# LedTile.net
KiCad netlist of a schematic drawn in EAGLE
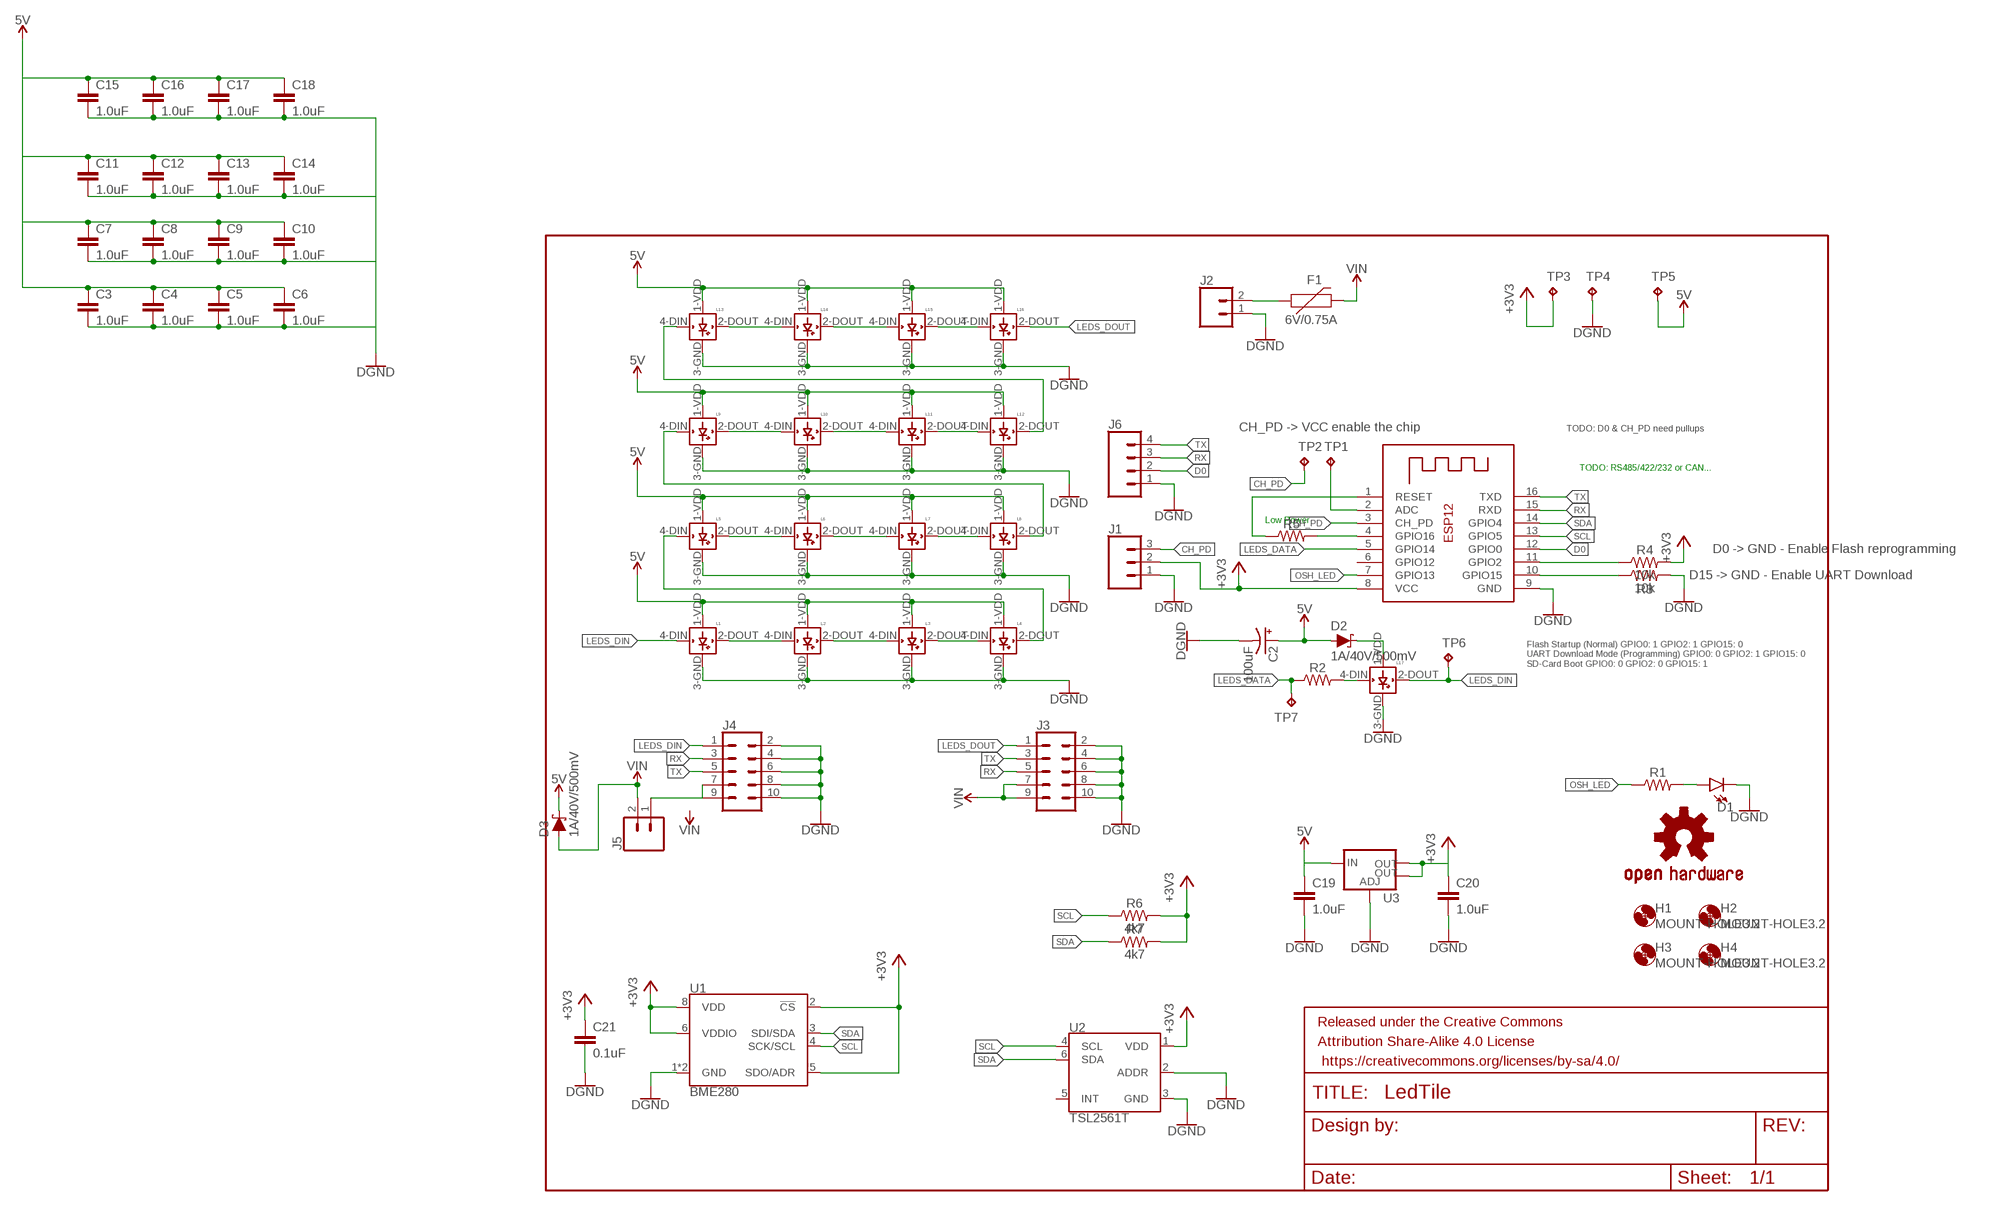
[diagram p0: schematic, sheet 1]

(export (version "E")
  (design (tool "Eeschema 10.0.6"))
  (components
    (comp (ref "C2")
      (value "100uF")
      (footprint "eagle-import:EIA7343")
      (libsource (lib "eagle-import") (part "100UF-POLAR-EIA7343-10V-10%(TANT)"))
    )
    (comp (ref "C3")
      (value "1.0uF")
      (footprint "eagle-import:0805")
      (libsource (lib "eagle-import") (part "1.0UF-0805-25V-(+80/-20%)"))
    )
    (comp (ref "C4")
      (value "1.0uF")
      (footprint "eagle-import:0805")
      (libsource (lib "eagle-import") (part "1.0UF-0805-25V-(+80/-20%)"))
    )
    (comp (ref "C5")
      (value "1.0uF")
      (footprint "eagle-import:0805")
      (libsource (lib "eagle-import") (part "1.0UF-0805-25V-(+80/-20%)"))
    )
    (comp (ref "C6")
      (value "1.0uF")
      (footprint "eagle-import:0805")
      (libsource (lib "eagle-import") (part "1.0UF-0805-25V-(+80/-20%)"))
    )
    (comp (ref "C7")
      (value "1.0uF")
      (footprint "eagle-import:0805")
      (libsource (lib "eagle-import") (part "1.0UF-0805-25V-(+80/-20%)"))
    )
    (comp (ref "C8")
      (value "1.0uF")
      (footprint "eagle-import:0805")
      (libsource (lib "eagle-import") (part "1.0UF-0805-25V-(+80/-20%)"))
    )
    (comp (ref "C9")
      (value "1.0uF")
      (footprint "eagle-import:0805")
      (libsource (lib "eagle-import") (part "1.0UF-0805-25V-(+80/-20%)"))
    )
    (comp (ref "C10")
      (value "1.0uF")
      (footprint "eagle-import:0805")
      (libsource (lib "eagle-import") (part "1.0UF-0805-25V-(+80/-20%)"))
    )
    (comp (ref "C11")
      (value "1.0uF")
      (footprint "eagle-import:0805")
      (libsource (lib "eagle-import") (part "1.0UF-0805-25V-(+80/-20%)"))
    )
    (comp (ref "C12")
      (value "1.0uF")
      (footprint "eagle-import:0805")
      (libsource (lib "eagle-import") (part "1.0UF-0805-25V-(+80/-20%)"))
    )
    (comp (ref "C13")
      (value "1.0uF")
      (footprint "eagle-import:0805")
      (libsource (lib "eagle-import") (part "1.0UF-0805-25V-(+80/-20%)"))
    )
    (comp (ref "C14")
      (value "1.0uF")
      (footprint "eagle-import:0805")
      (libsource (lib "eagle-import") (part "1.0UF-0805-25V-(+80/-20%)"))
    )
    (comp (ref "C15")
      (value "1.0uF")
      (footprint "eagle-import:0805")
      (libsource (lib "eagle-import") (part "1.0UF-0805-25V-(+80/-20%)"))
    )
    (comp (ref "C16")
      (value "1.0uF")
      (footprint "eagle-import:0805")
      (libsource (lib "eagle-import") (part "1.0UF-0805-25V-(+80/-20%)"))
    )
    (comp (ref "C17")
      (value "1.0uF")
      (footprint "eagle-import:0805")
      (libsource (lib "eagle-import") (part "1.0UF-0805-25V-(+80/-20%)"))
    )
    (comp (ref "C18")
      (value "1.0uF")
      (footprint "eagle-import:0805")
      (libsource (lib "eagle-import") (part "1.0UF-0805-25V-(+80/-20%)"))
    )
    (comp (ref "C19")
      (value "1.0uF")
      (footprint "eagle-import:0805")
      (libsource (lib "eagle-import") (part "1.0UF-0805-25V-(+80/-20%)"))
    )
    (comp (ref "C20")
      (value "1.0uF")
      (footprint "eagle-import:0805")
      (libsource (lib "eagle-import") (part "1.0UF-0805-25V-(+80/-20%)"))
    )
    (comp (ref "C21")
      (value "0.1uF")
      (footprint "eagle-import:0805")
      (libsource (lib "eagle-import") (part "1.0UF-0805-25V-(+80/-20%)"))
    )
    (comp (ref "D1")
      (value "LED1206-BOTTOM")
      (footprint "eagle-import:LED-1206-BOTTOM")
      (libsource (lib "eagle-import") (part "LED1206-BOTTOM"))
    )
    (comp (ref "D2")
      (value "1A/40V/500mV")
      (footprint "eagle-import:SMA-DIODE")
      (libsource (lib "eagle-import") (part "DIODE-SCHOTTKY-SS14"))
    )
    (comp (ref "D3")
      (value "1A/40V/500mV")
      (footprint "eagle-import:SMA-DIODE")
      (libsource (lib "eagle-import") (part "DIODE-SCHOTTKY-SS14"))
    )
    (comp (ref "F1")
      (value "6V/0.75A")
      (footprint "eagle-import:1206")
      (libsource (lib "eagle-import") (part "PPTC_THREE-QUARTER-AMP"))
    )
    (comp (ref "FRAME1")
      (value "FRAME-LETTER")
      (footprint "eagle-import:CREATIVE_COMMONS")
      (libsource (lib "eagle-import") (part "FRAME-LETTER"))
    )
    (comp (ref "H1")
      (value "MOUNT-HOLE3.2")
      (footprint "eagle-import:3,2")
      (libsource (lib "eagle-import") (part "MOUNT-HOLE3.2"))
    )
    (comp (ref "H2")
      (value "MOUNT-HOLE3.2")
      (footprint "eagle-import:3,2")
      (libsource (lib "eagle-import") (part "MOUNT-HOLE3.2"))
    )
    (comp (ref "H3")
      (value "MOUNT-HOLE3.2")
      (footprint "eagle-import:3,2")
      (libsource (lib "eagle-import") (part "MOUNT-HOLE3.2"))
    )
    (comp (ref "H4")
      (value "MOUNT-HOLE3.2")
      (footprint "eagle-import:3,2")
      (libsource (lib "eagle-import") (part "MOUNT-HOLE3.2"))
    )
    (comp (ref "J1")
      (value "CONN_031X03_NO_SILK")
      (footprint "eagle-import:1X03_NO_SILK")
      (libsource (lib "eagle-import") (part "CONN_031X03_NO_SILK"))
    )
    (comp (ref "J2")
      (value "CONN_025MM")
      (footprint "eagle-import:SCREWTERMINAL-5MM-2")
      (libsource (lib "eagle-import") (part "CONN_025MM"))
    )
    (comp (ref "J3")
      (value "CONN_05X2RA")
      (footprint "eagle-import:2X5-RA")
      (libsource (lib "eagle-import") (part "CONN_05X2RA"))
    )
    (comp (ref "J4")
      (value "CONN_05X2RA")
      (footprint "eagle-import:2X5-RA")
      (libsource (lib "eagle-import") (part "CONN_05X2RA"))
    )
    (comp (ref "J5")
      (value "CONN_02")
      (footprint "eagle-import:1X02")
      (libsource (lib "eagle-import") (part "CONN_02"))
    )
    (comp (ref "J6")
      (value "CONN_04")
      (footprint "eagle-import:1X04")
      (libsource (lib "eagle-import") (part "CONN_04"))
    )
    (comp (ref "L1")
      (value "WS2812B")
      (footprint "eagle-import:WS2812B")
      (libsource (lib "eagle-import") (part "WS2812B"))
    )
    (comp (ref "L2")
      (value "WS2812B")
      (footprint "eagle-import:WS2812B")
      (libsource (lib "eagle-import") (part "WS2812B"))
    )
    (comp (ref "L3")
      (value "WS2812B")
      (footprint "eagle-import:WS2812B")
      (libsource (lib "eagle-import") (part "WS2812B"))
    )
    (comp (ref "L4")
      (value "WS2812B")
      (footprint "eagle-import:WS2812B")
      (libsource (lib "eagle-import") (part "WS2812B"))
    )
    (comp (ref "L5")
      (value "WS2812B")
      (footprint "eagle-import:WS2812B")
      (libsource (lib "eagle-import") (part "WS2812B"))
    )
    (comp (ref "L6")
      (value "WS2812B")
      (footprint "eagle-import:WS2812B")
      (libsource (lib "eagle-import") (part "WS2812B"))
    )
    (comp (ref "L7")
      (value "WS2812B")
      (footprint "eagle-import:WS2812B")
      (libsource (lib "eagle-import") (part "WS2812B"))
    )
    (comp (ref "L8")
      (value "WS2812B")
      (footprint "eagle-import:WS2812B")
      (libsource (lib "eagle-import") (part "WS2812B"))
    )
    (comp (ref "L9")
      (value "WS2812B")
      (footprint "eagle-import:WS2812B")
      (libsource (lib "eagle-import") (part "WS2812B"))
    )
    (comp (ref "L10")
      (value "WS2812B")
      (footprint "eagle-import:WS2812B")
      (libsource (lib "eagle-import") (part "WS2812B"))
    )
    (comp (ref "L11")
      (value "WS2812B")
      (footprint "eagle-import:WS2812B")
      (libsource (lib "eagle-import") (part "WS2812B"))
    )
    (comp (ref "L12")
      (value "WS2812B")
      (footprint "eagle-import:WS2812B")
      (libsource (lib "eagle-import") (part "WS2812B"))
    )
    (comp (ref "L13")
      (value "WS2812B")
      (footprint "eagle-import:WS2812B")
      (libsource (lib "eagle-import") (part "WS2812B"))
    )
    (comp (ref "L14")
      (value "WS2812B")
      (footprint "eagle-import:WS2812B")
      (libsource (lib "eagle-import") (part "WS2812B"))
    )
    (comp (ref "L15")
      (value "WS2812B")
      (footprint "eagle-import:WS2812B")
      (libsource (lib "eagle-import") (part "WS2812B"))
    )
    (comp (ref "L16")
      (value "WS2812B")
      (footprint "eagle-import:WS2812B")
      (libsource (lib "eagle-import") (part "WS2812B"))
    )
    (comp (ref "L17")
      (value "WS2812B")
      (footprint "eagle-import:WS2812B")
      (libsource (lib "eagle-import") (part "WS2812B"))
    )
    (comp (ref "LOGO1")
      (value "OSHW-LOGOL")
      (footprint "eagle-import:OSHW-LOGO-L")
      (libsource (lib "eagle-import") (part "OSHW-LOGOL"))
    )
    (comp (ref "R1")
      (value "RESISTOR0805")
      (footprint "eagle-import:0805")
      (libsource (lib "eagle-import") (part "RESISTOR0805"))
    )
    (comp (ref "R2")
      (value "RESISTOR0805")
      (footprint "eagle-import:0805")
      (libsource (lib "eagle-import") (part "RESISTOR0805"))
    )
    (comp (ref "R3")
      (value "10k")
      (footprint "eagle-import:0805")
      (libsource (lib "eagle-import") (part "RESISTOR0805"))
    )
    (comp (ref "R4")
      (value "10k")
      (footprint "eagle-import:0805")
      (libsource (lib "eagle-import") (part "RESISTOR0805"))
    )
    (comp (ref "R5")
      (value "RESISTOR0805")
      (footprint "eagle-import:0805")
      (libsource (lib "eagle-import") (part "RESISTOR0805"))
    )
    (comp (ref "R6")
      (value "4k7")
      (footprint "eagle-import:0805")
      (libsource (lib "eagle-import") (part "RESISTOR0805"))
    )
    (comp (ref "R7")
      (value "4k7")
      (footprint "eagle-import:0805")
      (libsource (lib "eagle-import") (part "RESISTOR0805"))
    )
    (comp (ref "TP1")
      (value "TPTP12R")
      (footprint "eagle-import:TP12R")
      (libsource (lib "eagle-import") (part "TPTP12R"))
    )
    (comp (ref "TP2")
      (value "TPTP12R")
      (footprint "eagle-import:TP12R")
      (libsource (lib "eagle-import") (part "TPTP12R"))
    )
    (comp (ref "TP3")
      (value "TPTP12R")
      (footprint "eagle-import:TP12R")
      (libsource (lib "eagle-import") (part "TPTP12R"))
    )
    (comp (ref "TP4")
      (value "TPTP12R")
      (footprint "eagle-import:TP12R")
      (libsource (lib "eagle-import") (part "TPTP12R"))
    )
    (comp (ref "TP5")
      (value "TPTP12R")
      (footprint "eagle-import:TP12R")
      (libsource (lib "eagle-import") (part "TPTP12R"))
    )
    (comp (ref "TP6")
      (value "TPTP12R")
      (footprint "eagle-import:TP12R")
      (libsource (lib "eagle-import") (part "TPTP12R"))
    )
    (comp (ref "TP7")
      (value "TPTP12R")
      (footprint "eagle-import:TP12R")
      (libsource (lib "eagle-import") (part "TPTP12R"))
    )
    (comp (ref "U1")
      (value "BME280")
      (footprint "eagle-import:LGA-8-2.5X2.5")
      (libsource (lib "eagle-import") (part "BME280"))
    )
    (comp (ref "U2")
      (value "TSL2561T")
      (footprint "eagle-import:TMB-6")
      (libsource (lib "eagle-import") (part "TSL2561T"))
    )
    (comp (ref "U3")
      (value "V_REG_LM1117SOT223")
      (footprint "eagle-import:SOT223")
      (libsource (lib "eagle-import") (part "V_REG_LM1117SOT223"))
    )
    (comp (ref "X1")
      (value "ESP-12")
      (footprint "eagle-import:ESP-12")
      (libsource (lib "eagle-import") (part "ESP-12"))
    )
  )
  (nets
    (net (code "1") (name "+3V3") (class "Default")
      (node (ref "C20") (pin "1") (pinfunction "1_1") (pintype "passive"))
      (node (ref "C21") (pin "1") (pinfunction "1_1") (pintype "passive"))
      (node (ref "J1") (pin "2") (pinfunction "2_2") (pintype "passive"))
      (node (ref "R4") (pin "2") (pinfunction "2_2") (pintype "passive"))
      (node (ref "R6") (pin "2") (pinfunction "2_2") (pintype "passive"))
      (node (ref "R7") (pin "2") (pinfunction "2_2") (pintype "passive"))
      (node (ref "TP3") (pin "TP") (pinfunction "TP_TP") (pintype "input"))
      (node (ref "U1") (pin "2") (pinfunction "~{CS}_2") (pintype "bidirectional"))
      (node (ref "U1") (pin "5") (pinfunction "SDO/ADR_5") (pintype "bidirectional"))
      (node (ref "U1") (pin "6") (pinfunction "VDDIO_6") (pintype "bidirectional"))
      (node (ref "U1") (pin "8") (pinfunction "VDD_8") (pintype "bidirectional"))
      (node (ref "U2") (pin "1") (pinfunction "VDD_1") (pintype "power_in"))
      (node (ref "U3") (pin "2") (pinfunction "OUT_2") (pintype "output"))
      (node (ref "U3") (pin "4") (pinfunction "OUT_4") (pintype "output"))
      (node (ref "X1") (pin "8") (pinfunction "VCC_8") (pintype "power_in"))
    )
    (net (code "2") (name "5V") (class "Default")
      (node (ref "C10") (pin "1") (pinfunction "1_1") (pintype "passive"))
      (node (ref "C11") (pin "1") (pinfunction "1_1") (pintype "passive"))
      (node (ref "C12") (pin "1") (pinfunction "1_1") (pintype "passive"))
      (node (ref "C13") (pin "1") (pinfunction "1_1") (pintype "passive"))
      (node (ref "C14") (pin "1") (pinfunction "1_1") (pintype "passive"))
      (node (ref "C15") (pin "1") (pinfunction "1_1") (pintype "passive"))
      (node (ref "C16") (pin "1") (pinfunction "1_1") (pintype "passive"))
      (node (ref "C17") (pin "1") (pinfunction "1_1") (pintype "passive"))
      (node (ref "C18") (pin "1") (pinfunction "1_1") (pintype "passive"))
      (node (ref "C19") (pin "1") (pinfunction "1_1") (pintype "passive"))
      (node (ref "C2") (pin "A") (pinfunction "+_A") (pintype "passive"))
      (node (ref "C3") (pin "1") (pinfunction "1_1") (pintype "passive"))
      (node (ref "C4") (pin "1") (pinfunction "1_1") (pintype "passive"))
      (node (ref "C5") (pin "1") (pinfunction "1_1") (pintype "passive"))
      (node (ref "C6") (pin "1") (pinfunction "1_1") (pintype "passive"))
      (node (ref "C7") (pin "1") (pinfunction "1_1") (pintype "passive"))
      (node (ref "C8") (pin "1") (pinfunction "1_1") (pintype "passive"))
      (node (ref "C9") (pin "1") (pinfunction "1_1") (pintype "passive"))
      (node (ref "D2") (pin "A") (pinfunction "A_A") (pintype "passive"))
      (node (ref "D3") (pin "C") (pinfunction "C_C") (pintype "passive"))
      (node (ref "L1") (pin "1-VDD") (pinfunction "VDD_1-VDD") (pintype "bidirectional"))
      (node (ref "L10") (pin "1-VDD") (pinfunction "VDD_1-VDD") (pintype "bidirectional"))
      (node (ref "L11") (pin "1-VDD") (pinfunction "VDD_1-VDD") (pintype "bidirectional"))
      (node (ref "L12") (pin "1-VDD") (pinfunction "VDD_1-VDD") (pintype "bidirectional"))
      (node (ref "L13") (pin "1-VDD") (pinfunction "VDD_1-VDD") (pintype "bidirectional"))
      (node (ref "L14") (pin "1-VDD") (pinfunction "VDD_1-VDD") (pintype "bidirectional"))
      (node (ref "L15") (pin "1-VDD") (pinfunction "VDD_1-VDD") (pintype "bidirectional"))
      (node (ref "L16") (pin "1-VDD") (pinfunction "VDD_1-VDD") (pintype "bidirectional"))
      (node (ref "L2") (pin "1-VDD") (pinfunction "VDD_1-VDD") (pintype "bidirectional"))
      (node (ref "L3") (pin "1-VDD") (pinfunction "VDD_1-VDD") (pintype "bidirectional"))
      (node (ref "L4") (pin "1-VDD") (pinfunction "VDD_1-VDD") (pintype "bidirectional"))
      (node (ref "L5") (pin "1-VDD") (pinfunction "VDD_1-VDD") (pintype "bidirectional"))
      (node (ref "L6") (pin "1-VDD") (pinfunction "VDD_1-VDD") (pintype "bidirectional"))
      (node (ref "L7") (pin "1-VDD") (pinfunction "VDD_1-VDD") (pintype "bidirectional"))
      (node (ref "L8") (pin "1-VDD") (pinfunction "VDD_1-VDD") (pintype "bidirectional"))
      (node (ref "L9") (pin "1-VDD") (pinfunction "VDD_1-VDD") (pintype "bidirectional"))
      (node (ref "TP5") (pin "TP") (pinfunction "TP_TP") (pintype "input"))
      (node (ref "U3") (pin "3") (pinfunction "IN_3") (pintype "input"))
    )
    (net (code "3") (name "CH_PD") (class "Default")
      (node (ref "J1") (pin "3") (pinfunction "3_3") (pintype "passive"))
      (node (ref "TP2") (pin "TP") (pinfunction "TP_TP") (pintype "input"))
      (node (ref "X1") (pin "3") (pinfunction "CH_PD_3") (pintype "input"))
    )
    (net (code "4") (name "D0") (class "Default")
      (node (ref "J6") (pin "2") (pinfunction "2_2") (pintype "passive"))
      (node (ref "X1") (pin "12") (pinfunction "GPIO0_12") (pintype "bidirectional"))
    )
    (net (code "5") (name "DGND") (class "Default")
      (node (ref "C10") (pin "2") (pinfunction "2_2") (pintype "passive"))
      (node (ref "C11") (pin "2") (pinfunction "2_2") (pintype "passive"))
      (node (ref "C12") (pin "2") (pinfunction "2_2") (pintype "passive"))
      (node (ref "C13") (pin "2") (pinfunction "2_2") (pintype "passive"))
      (node (ref "C14") (pin "2") (pinfunction "2_2") (pintype "passive"))
      (node (ref "C15") (pin "2") (pinfunction "2_2") (pintype "passive"))
      (node (ref "C16") (pin "2") (pinfunction "2_2") (pintype "passive"))
      (node (ref "C17") (pin "2") (pinfunction "2_2") (pintype "passive"))
      (node (ref "C18") (pin "2") (pinfunction "2_2") (pintype "passive"))
      (node (ref "C19") (pin "2") (pinfunction "2_2") (pintype "passive"))
      (node (ref "C2") (pin "C") (pinfunction "-_C") (pintype "passive"))
      (node (ref "C20") (pin "2") (pinfunction "2_2") (pintype "passive"))
      (node (ref "C21") (pin "2") (pinfunction "2_2") (pintype "passive"))
      (node (ref "C3") (pin "2") (pinfunction "2_2") (pintype "passive"))
      (node (ref "C4") (pin "2") (pinfunction "2_2") (pintype "passive"))
      (node (ref "C5") (pin "2") (pinfunction "2_2") (pintype "passive"))
      (node (ref "C6") (pin "2") (pinfunction "2_2") (pintype "passive"))
      (node (ref "C7") (pin "2") (pinfunction "2_2") (pintype "passive"))
      (node (ref "C8") (pin "2") (pinfunction "2_2") (pintype "passive"))
      (node (ref "C9") (pin "2") (pinfunction "2_2") (pintype "passive"))
      (node (ref "D1") (pin "C") (pinfunction "C_C") (pintype "passive"))
      (node (ref "J1") (pin "1") (pinfunction "1_1") (pintype "passive"))
      (node (ref "J2") (pin "1") (pinfunction "1_1") (pintype "passive"))
      (node (ref "J3") (pin "10") (pinfunction "10_10") (pintype "passive"))
      (node (ref "J3") (pin "2") (pinfunction "2_2") (pintype "passive"))
      (node (ref "J3") (pin "4") (pinfunction "4_4") (pintype "passive"))
      (node (ref "J3") (pin "6") (pinfunction "6_6") (pintype "passive"))
      (node (ref "J3") (pin "8") (pinfunction "8_8") (pintype "passive"))
      (node (ref "J4") (pin "10") (pinfunction "10_10") (pintype "passive"))
      (node (ref "J4") (pin "2") (pinfunction "2_2") (pintype "passive"))
      (node (ref "J4") (pin "4") (pinfunction "4_4") (pintype "passive"))
      (node (ref "J4") (pin "6") (pinfunction "6_6") (pintype "passive"))
      (node (ref "J4") (pin "8") (pinfunction "8_8") (pintype "passive"))
      (node (ref "J6") (pin "1") (pinfunction "1_1") (pintype "passive"))
      (node (ref "L1") (pin "3-GND") (pinfunction "GND_3-GND") (pintype "bidirectional"))
      (node (ref "L10") (pin "3-GND") (pinfunction "GND_3-GND") (pintype "bidirectional"))
      (node (ref "L11") (pin "3-GND") (pinfunction "GND_3-GND") (pintype "bidirectional"))
      (node (ref "L12") (pin "3-GND") (pinfunction "GND_3-GND") (pintype "bidirectional"))
      (node (ref "L13") (pin "3-GND") (pinfunction "GND_3-GND") (pintype "bidirectional"))
      (node (ref "L14") (pin "3-GND") (pinfunction "GND_3-GND") (pintype "bidirectional"))
      (node (ref "L15") (pin "3-GND") (pinfunction "GND_3-GND") (pintype "bidirectional"))
      (node (ref "L16") (pin "3-GND") (pinfunction "GND_3-GND") (pintype "bidirectional"))
      (node (ref "L17") (pin "3-GND") (pinfunction "GND_3-GND") (pintype "bidirectional"))
      (node (ref "L2") (pin "3-GND") (pinfunction "GND_3-GND") (pintype "bidirectional"))
      (node (ref "L3") (pin "3-GND") (pinfunction "GND_3-GND") (pintype "bidirectional"))
      (node (ref "L4") (pin "3-GND") (pinfunction "GND_3-GND") (pintype "bidirectional"))
      (node (ref "L5") (pin "3-GND") (pinfunction "GND_3-GND") (pintype "bidirectional"))
      (node (ref "L6") (pin "3-GND") (pinfunction "GND_3-GND") (pintype "bidirectional"))
      (node (ref "L7") (pin "3-GND") (pinfunction "GND_3-GND") (pintype "bidirectional"))
      (node (ref "L8") (pin "3-GND") (pinfunction "GND_3-GND") (pintype "bidirectional"))
      (node (ref "L9") (pin "3-GND") (pinfunction "GND_3-GND") (pintype "bidirectional"))
      (node (ref "R3") (pin "2") (pinfunction "2_2") (pintype "passive"))
      (node (ref "TP4") (pin "TP") (pinfunction "TP_TP") (pintype "input"))
      (node (ref "U1") (pin "1") (pinfunction "GND_1") (pintype "bidirectional"))
      (node (ref "U1") (pin "7") (pinfunction "GND_7") (pintype "bidirectional"))
      (node (ref "U2") (pin "2") (pinfunction "ADDR_2") (pintype "input"))
      (node (ref "U2") (pin "3") (pinfunction "GND_3") (pintype "power_in"))
      (node (ref "U3") (pin "1") (pinfunction "ADJ_1") (pintype "input"))
      (node (ref "X1") (pin "9") (pinfunction "GND_9") (pintype "power_in"))
    )
    (net (code "6") (name "LEDS_DATA") (class "Default")
      (node (ref "R2") (pin "1") (pinfunction "1_1") (pintype "passive"))
      (node (ref "TP7") (pin "TP") (pinfunction "TP_TP") (pintype "input"))
      (node (ref "X1") (pin "5") (pinfunction "GPIO14_5") (pintype "bidirectional"))
    )
    (net (code "7") (name "LEDS_DIN") (class "Default")
      (node (ref "J4") (pin "1") (pinfunction "1_1") (pintype "passive"))
      (node (ref "L1") (pin "4-DIN") (pinfunction "DIN_4-DIN") (pintype "input"))
      (node (ref "L17") (pin "2-DOUT") (pinfunction "DOUT_2-DOUT") (pintype "output"))
      (node (ref "TP6") (pin "TP") (pinfunction "TP_TP") (pintype "input"))
    )
    (net (code "8") (name "LEDS_DOUT") (class "Default")
      (node (ref "J3") (pin "1") (pinfunction "1_1") (pintype "passive"))
      (node (ref "L16") (pin "2-DOUT") (pinfunction "DOUT_2-DOUT") (pintype "output"))
    )
    (net (code "9") (name "Net-(D1-PadA)") (class "Default")
      (node (ref "D1") (pin "A") (pinfunction "A_A") (pintype "passive"))
      (node (ref "R1") (pin "2") (pinfunction "2_2") (pintype "passive"))
    )
    (net (code "10") (name "Net-(F1-Pad1)") (class "Default")
      (node (ref "F1") (pin "1") (pinfunction "1_1") (pintype "bidirectional"))
      (node (ref "J2") (pin "2") (pinfunction "2_2") (pintype "passive"))
    )
    (net (code "11") (name "Net-(J4-Pad7)") (class "Default")
      (node (ref "J4") (pin "7") (pinfunction "7_7") (pintype "passive"))
      (node (ref "J4") (pin "9") (pinfunction "9_9") (pintype "passive"))
      (node (ref "J5") (pin "1") (pinfunction "1_1") (pintype "passive"))
    )
    (net (code "12") (name "Net-(L1-DOUT)") (class "Default")
      (node (ref "L1") (pin "2-DOUT") (pinfunction "DOUT_2-DOUT") (pintype "output"))
      (node (ref "L2") (pin "4-DIN") (pinfunction "DIN_4-DIN") (pintype "input"))
    )
    (net (code "13") (name "Net-(L2-DOUT)") (class "Default")
      (node (ref "L2") (pin "2-DOUT") (pinfunction "DOUT_2-DOUT") (pintype "output"))
      (node (ref "L3") (pin "4-DIN") (pinfunction "DIN_4-DIN") (pintype "input"))
    )
    (net (code "14") (name "Net-(L3-DOUT)") (class "Default")
      (node (ref "L3") (pin "2-DOUT") (pinfunction "DOUT_2-DOUT") (pintype "output"))
      (node (ref "L4") (pin "4-DIN") (pinfunction "DIN_4-DIN") (pintype "input"))
    )
    (net (code "15") (name "Net-(L4-DOUT)") (class "Default")
      (node (ref "L4") (pin "2-DOUT") (pinfunction "DOUT_2-DOUT") (pintype "output"))
      (node (ref "L5") (pin "4-DIN") (pinfunction "DIN_4-DIN") (pintype "input"))
    )
    (net (code "16") (name "Net-(L5-DOUT)") (class "Default")
      (node (ref "L5") (pin "2-DOUT") (pinfunction "DOUT_2-DOUT") (pintype "output"))
      (node (ref "L6") (pin "4-DIN") (pinfunction "DIN_4-DIN") (pintype "input"))
    )
    (net (code "17") (name "Net-(L6-DOUT)") (class "Default")
      (node (ref "L6") (pin "2-DOUT") (pinfunction "DOUT_2-DOUT") (pintype "output"))
      (node (ref "L7") (pin "4-DIN") (pinfunction "DIN_4-DIN") (pintype "input"))
    )
    (net (code "18") (name "Net-(L7-DOUT)") (class "Default")
      (node (ref "L7") (pin "2-DOUT") (pinfunction "DOUT_2-DOUT") (pintype "output"))
      (node (ref "L8") (pin "4-DIN") (pinfunction "DIN_4-DIN") (pintype "input"))
    )
    (net (code "19") (name "Net-(L8-DOUT)") (class "Default")
      (node (ref "L8") (pin "2-DOUT") (pinfunction "DOUT_2-DOUT") (pintype "output"))
      (node (ref "L9") (pin "4-DIN") (pinfunction "DIN_4-DIN") (pintype "input"))
    )
    (net (code "20") (name "Net-(L10-DIN)") (class "Default")
      (node (ref "L10") (pin "4-DIN") (pinfunction "DIN_4-DIN") (pintype "input"))
      (node (ref "L9") (pin "2-DOUT") (pinfunction "DOUT_2-DOUT") (pintype "output"))
    )
    (net (code "21") (name "Net-(L10-DOUT)") (class "Default")
      (node (ref "L10") (pin "2-DOUT") (pinfunction "DOUT_2-DOUT") (pintype "output"))
      (node (ref "L11") (pin "4-DIN") (pinfunction "DIN_4-DIN") (pintype "input"))
    )
    (net (code "22") (name "Net-(L11-DOUT)") (class "Default")
      (node (ref "L11") (pin "2-DOUT") (pinfunction "DOUT_2-DOUT") (pintype "output"))
      (node (ref "L12") (pin "4-DIN") (pinfunction "DIN_4-DIN") (pintype "input"))
    )
    (net (code "23") (name "Net-(L12-DOUT)") (class "Default")
      (node (ref "L12") (pin "2-DOUT") (pinfunction "DOUT_2-DOUT") (pintype "output"))
      (node (ref "L13") (pin "4-DIN") (pinfunction "DIN_4-DIN") (pintype "input"))
    )
    (net (code "24") (name "Net-(L13-DOUT)") (class "Default")
      (node (ref "L13") (pin "2-DOUT") (pinfunction "DOUT_2-DOUT") (pintype "output"))
      (node (ref "L14") (pin "4-DIN") (pinfunction "DIN_4-DIN") (pintype "input"))
    )
    (net (code "25") (name "Net-(L14-DOUT)") (class "Default")
      (node (ref "L14") (pin "2-DOUT") (pinfunction "DOUT_2-DOUT") (pintype "output"))
      (node (ref "L15") (pin "4-DIN") (pinfunction "DIN_4-DIN") (pintype "input"))
    )
    (net (code "26") (name "Net-(L15-DOUT)") (class "Default")
      (node (ref "L15") (pin "2-DOUT") (pinfunction "DOUT_2-DOUT") (pintype "output"))
      (node (ref "L16") (pin "4-DIN") (pinfunction "DIN_4-DIN") (pintype "input"))
    )
    (net (code "27") (name "Net-(L17-DIN)") (class "Default")
      (node (ref "L17") (pin "4-DIN") (pinfunction "DIN_4-DIN") (pintype "input"))
      (node (ref "R2") (pin "2") (pinfunction "2_2") (pintype "passive"))
    )
    (net (code "28") (name "Net-(L17-VDD)") (class "Default")
      (node (ref "D2") (pin "C") (pinfunction "C_C") (pintype "passive"))
      (node (ref "L17") (pin "1-VDD") (pinfunction "VDD_1-VDD") (pintype "bidirectional"))
    )
    (net (code "29") (name "Net-(X1-ADC)") (class "Default")
      (node (ref "TP1") (pin "TP") (pinfunction "TP_TP") (pintype "input"))
      (node (ref "X1") (pin "2") (pinfunction "ADC_2") (pintype "passive"))
    )
    (net (code "30") (name "Net-(X1-GPIO2)") (class "Default")
      (node (ref "R4") (pin "1") (pinfunction "1_1") (pintype "passive"))
      (node (ref "X1") (pin "11") (pinfunction "GPIO2_11") (pintype "bidirectional"))
    )
    (net (code "31") (name "Net-(X1-GPIO15)") (class "Default")
      (node (ref "R3") (pin "1") (pinfunction "1_1") (pintype "passive"))
      (node (ref "X1") (pin "10") (pinfunction "GPIO15_10") (pintype "bidirectional"))
    )
    (net (code "32") (name "Net-(X1-GPIO16)") (class "Default")
      (node (ref "R5") (pin "2") (pinfunction "2_2") (pintype "passive"))
      (node (ref "X1") (pin "4") (pinfunction "GPIO16_4") (pintype "bidirectional"))
    )
    (net (code "33") (name "Net-(X1-RESET)") (class "Default")
      (node (ref "R5") (pin "1") (pinfunction "1_1") (pintype "passive"))
      (node (ref "X1") (pin "1") (pinfunction "RESET_1") (pintype "input"))
    )
    (net (code "34") (name "OSH_LED") (class "Default")
      (node (ref "R1") (pin "1") (pinfunction "1_1") (pintype "passive"))
      (node (ref "X1") (pin "7") (pinfunction "GPIO13_7") (pintype "bidirectional"))
    )
    (net (code "35") (name "RX") (class "Default")
      (node (ref "J3") (pin "5") (pinfunction "5_5") (pintype "passive"))
      (node (ref "J4") (pin "3") (pinfunction "3_3") (pintype "passive"))
      (node (ref "J6") (pin "3") (pinfunction "3_3") (pintype "passive"))
      (node (ref "X1") (pin "15") (pinfunction "RXD_15") (pintype "input"))
    )
    (net (code "36") (name "SCL") (class "Default")
      (node (ref "R6") (pin "1") (pinfunction "1_1") (pintype "passive"))
      (node (ref "U1") (pin "4") (pinfunction "SCK/SCL_4") (pintype "bidirectional"))
      (node (ref "U2") (pin "4") (pinfunction "SCL_4") (pintype "input"))
      (node (ref "X1") (pin "13") (pinfunction "GPIO5_13") (pintype "bidirectional"))
    )
    (net (code "37") (name "SDA") (class "Default")
      (node (ref "R7") (pin "1") (pinfunction "1_1") (pintype "passive"))
      (node (ref "U1") (pin "3") (pinfunction "SDI/SDA_3") (pintype "bidirectional"))
      (node (ref "U2") (pin "6") (pinfunction "SDA_6") (pintype "bidirectional"))
      (node (ref "X1") (pin "14") (pinfunction "GPIO4_14") (pintype "bidirectional"))
    )
    (net (code "38") (name "TX") (class "Default")
      (node (ref "J3") (pin "3") (pinfunction "3_3") (pintype "passive"))
      (node (ref "J4") (pin "5") (pinfunction "5_5") (pintype "passive"))
      (node (ref "J6") (pin "4") (pinfunction "4_4") (pintype "passive"))
      (node (ref "X1") (pin "16") (pinfunction "TXD_16") (pintype "output"))
    )
    (net (code "39") (name "VIN") (class "Default")
      (node (ref "D3") (pin "A") (pinfunction "A_A") (pintype "passive"))
      (node (ref "F1") (pin "2") (pinfunction "2_2") (pintype "bidirectional"))
      (node (ref "J3") (pin "7") (pinfunction "7_7") (pintype "passive"))
      (node (ref "J3") (pin "9") (pinfunction "9_9") (pintype "passive"))
      (node (ref "J5") (pin "2") (pinfunction "2_2") (pintype "passive"))
    )
    (net (code "40") (name "unconnected-(U2-INT-Pad5)") (class "Default")
      (node (ref "U2") (pin "5") (pinfunction "INT_5") (pintype "output"))
    )
    (net (code "41") (name "unconnected-(X1-GPIO12-Pad6)") (class "Default")
      (node (ref "X1") (pin "6") (pinfunction "GPIO12_6") (pintype "bidirectional"))
    )
  )
)
